# 20260106.net
KiCad netlist of a schematic drawn in EasyEDA Pro
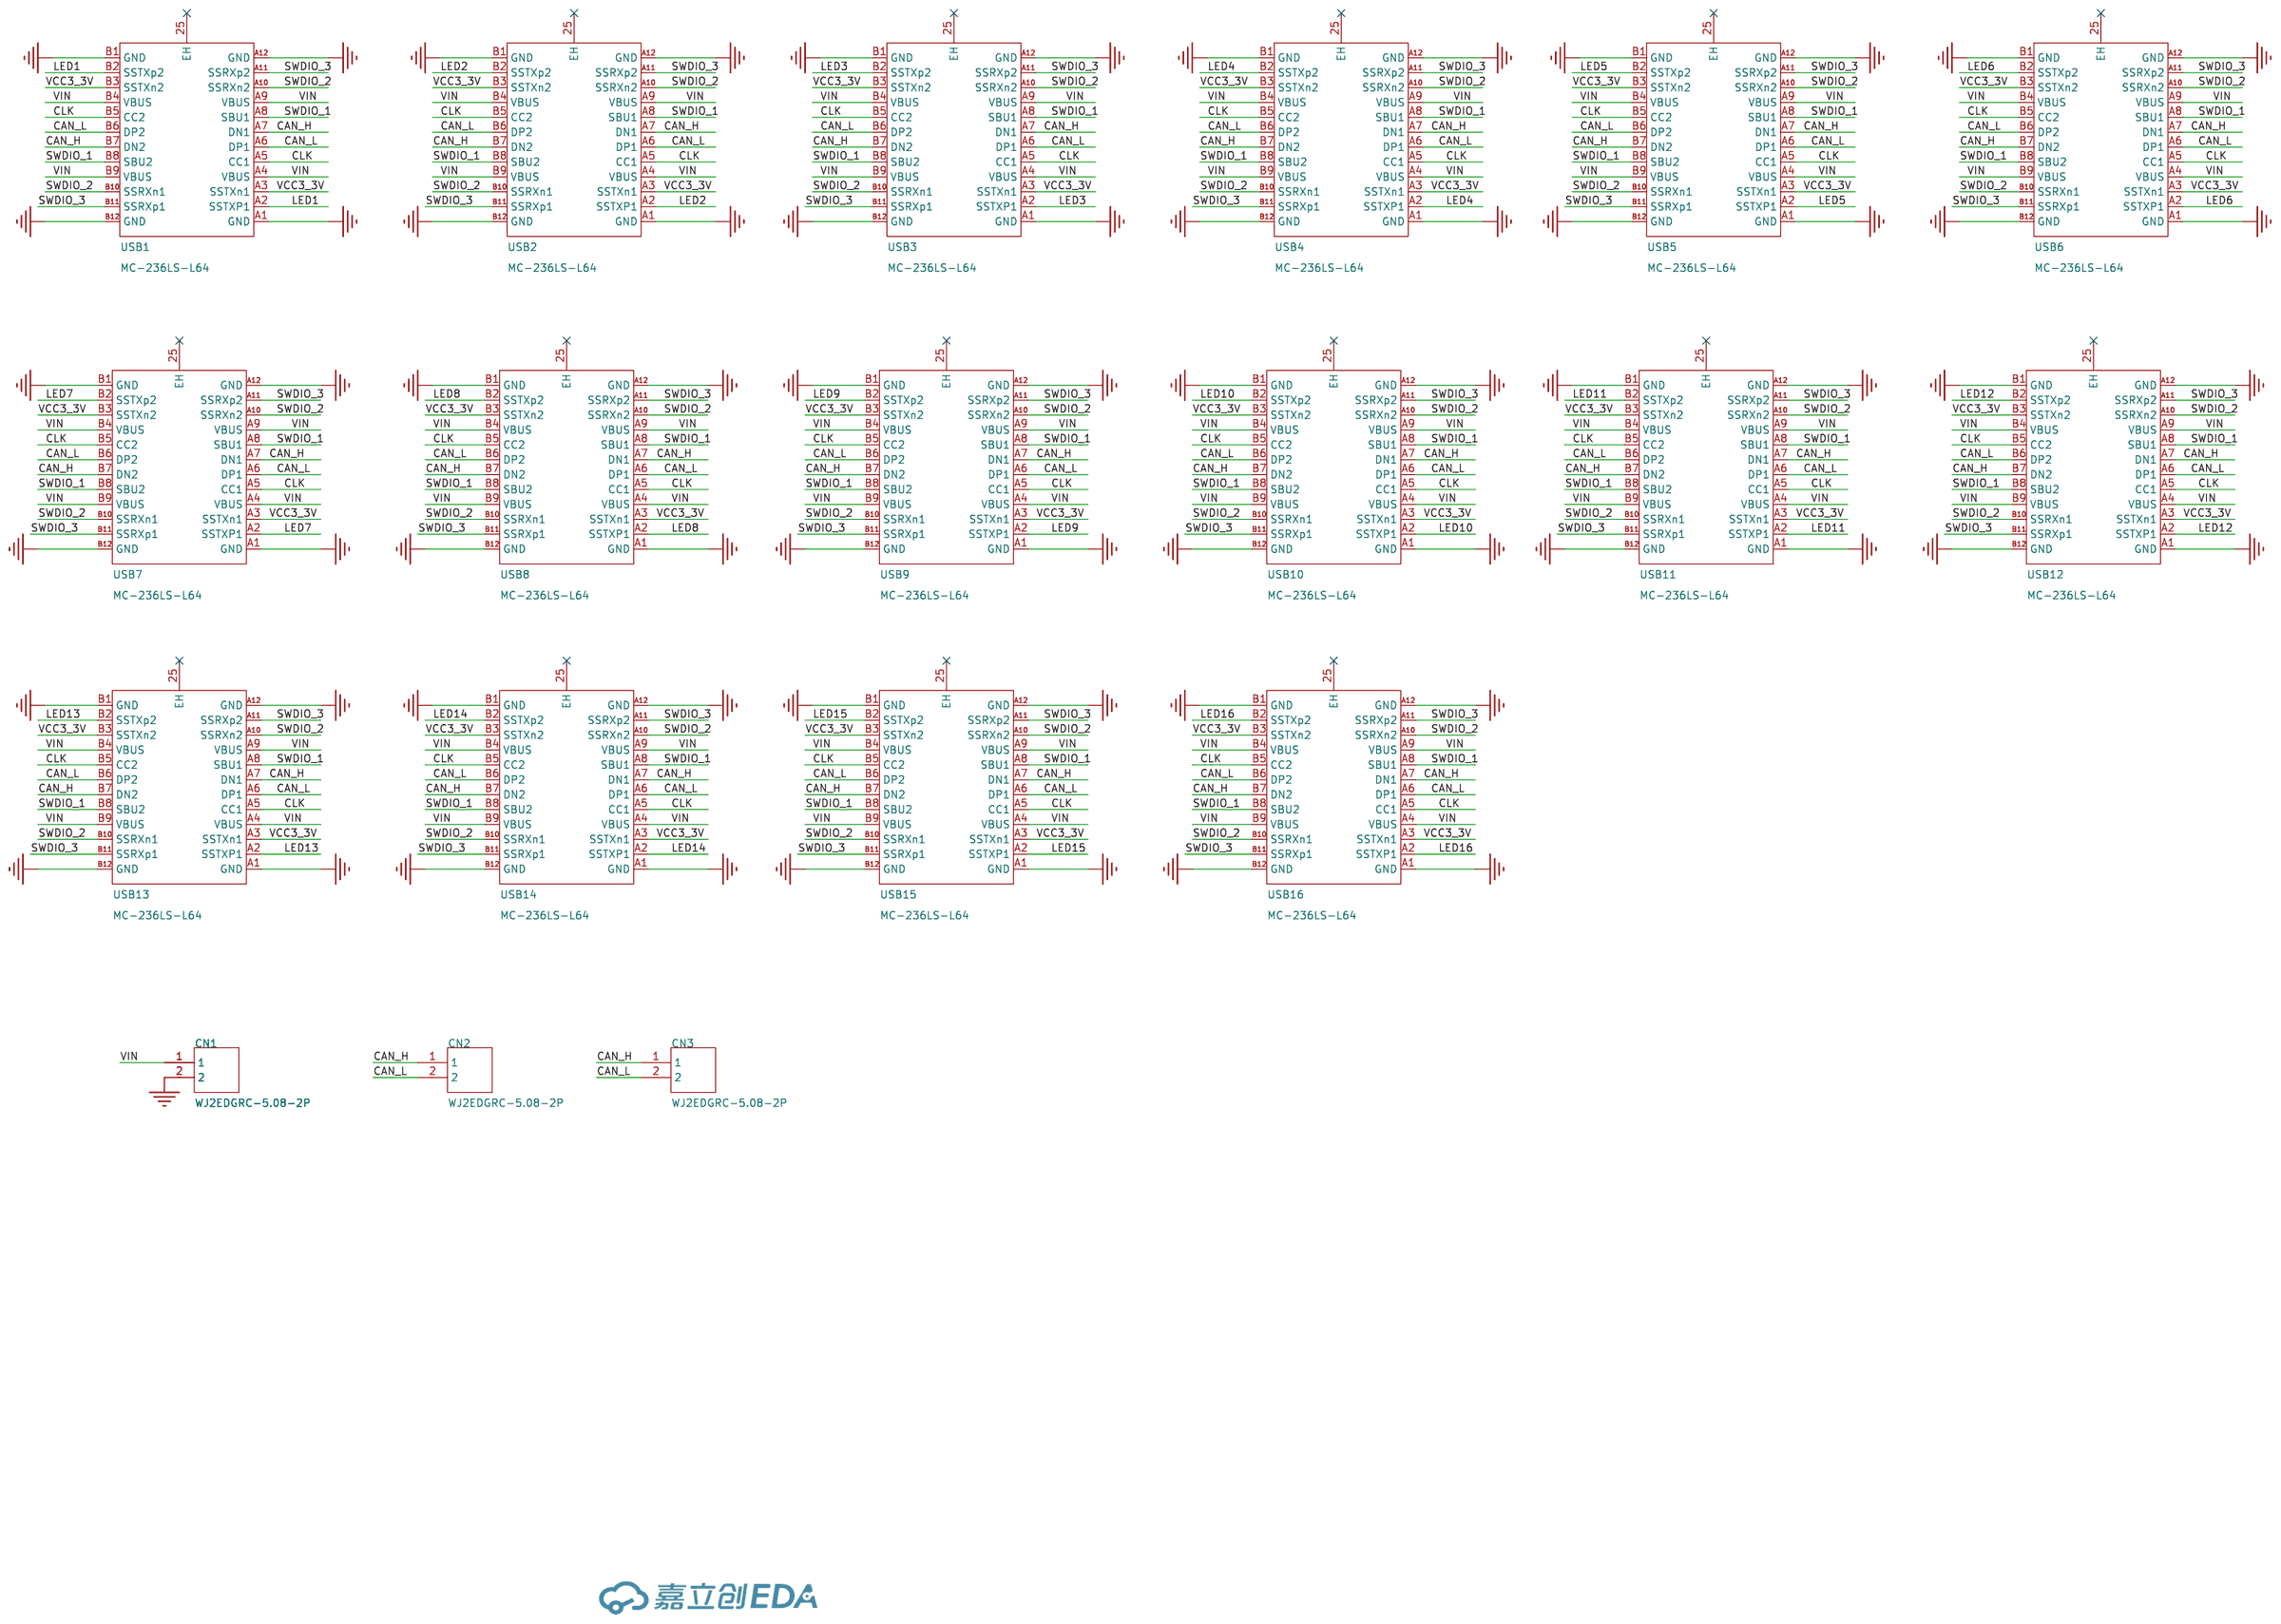
[diagram p0: schematic sheet]

(export (version "E")
  (design (tool "Eeschema 10.0.6"))
  (components
    (comp (ref "CN1")
      (value "WJ2EDGRC-5.08-2P")
      (footprint "easyedapro:CONN-TH_2P-P5.08_WJ2EDGRC-5.08-2P")
      (fields (field (name "Manufacturer") "KANGNEX(康奈克斯电气)"))
      (libsource (lib "easyedapro") (part "WJ2EDGRC-5.08-2P"))
    )
    (comp (ref "CN2")
      (value "WJ2EDGRC-5.08-2P")
      (footprint "easyedapro:CONN-TH_2P-P5.08_WJ2EDGRC-5.08-2P")
      (fields (field (name "Manufacturer") "KANGNEX(康奈克斯电气)"))
      (libsource (lib "easyedapro") (part "WJ2EDGRC-5.08-2P"))
    )
    (comp (ref "CN3")
      (value "WJ2EDGRC-5.08-2P")
      (footprint "easyedapro:CONN-TH_2P-P5.08_WJ2EDGRC-5.08-2P")
      (fields (field (name "Manufacturer") "KANGNEX(康奈克斯电气)"))
      (libsource (lib "easyedapro") (part "WJ2EDGRC-5.08-2P"))
    )
    (comp (ref "USB1")
      (value "MC-236LS-L64")
      (footprint "easyedapro:TYPE-C-USB-SMD_TYPE-C-31-M-06")
      (description "连接器类型:Type-C;协议标准:USB 3.1;公母:母;安装方式:立贴;触点数量:24P;端口数量:1;额定电流 - 电源:5A;工作温度:-25°C~+85°C;")
      (fields (field (name "Manufacturer") "HANBO(汉博)"))
      (libsource (lib "easyedapro") (part "MC-236LS-L64"))
    )
    (comp (ref "USB2")
      (value "MC-236LS-L64")
      (footprint "easyedapro:TYPE-C-USB-SMD_TYPE-C-31-M-06")
      (description "连接器类型:Type-C;协议标准:USB 3.1;公母:母;安装方式:立贴;触点数量:24P;端口数量:1;额定电流 - 电源:5A;工作温度:-25°C~+85°C;")
      (fields (field (name "Manufacturer") "HANBO(汉博)"))
      (libsource (lib "easyedapro") (part "MC-236LS-L64"))
    )
    (comp (ref "USB3")
      (value "MC-236LS-L64")
      (footprint "easyedapro:TYPE-C-USB-SMD_TYPE-C-31-M-06")
      (description "连接器类型:Type-C;协议标准:USB 3.1;公母:母;安装方式:立贴;触点数量:24P;端口数量:1;额定电流 - 电源:5A;工作温度:-25°C~+85°C;")
      (fields (field (name "Manufacturer") "HANBO(汉博)"))
      (libsource (lib "easyedapro") (part "MC-236LS-L64"))
    )
    (comp (ref "USB4")
      (value "MC-236LS-L64")
      (footprint "easyedapro:TYPE-C-USB-SMD_TYPE-C-31-M-06")
      (description "连接器类型:Type-C;协议标准:USB 3.1;公母:母;安装方式:立贴;触点数量:24P;端口数量:1;额定电流 - 电源:5A;工作温度:-25°C~+85°C;")
      (fields (field (name "Manufacturer") "HANBO(汉博)"))
      (libsource (lib "easyedapro") (part "MC-236LS-L64"))
    )
    (comp (ref "USB5")
      (value "MC-236LS-L64")
      (footprint "easyedapro:TYPE-C-USB-SMD_TYPE-C-31-M-06")
      (description "连接器类型:Type-C;协议标准:USB 3.1;公母:母;安装方式:立贴;触点数量:24P;端口数量:1;额定电流 - 电源:5A;工作温度:-25°C~+85°C;")
      (fields (field (name "Manufacturer") "HANBO(汉博)"))
      (libsource (lib "easyedapro") (part "MC-236LS-L64"))
    )
    (comp (ref "USB6")
      (value "MC-236LS-L64")
      (footprint "easyedapro:TYPE-C-USB-SMD_TYPE-C-31-M-06")
      (description "连接器类型:Type-C;协议标准:USB 3.1;公母:母;安装方式:立贴;触点数量:24P;端口数量:1;额定电流 - 电源:5A;工作温度:-25°C~+85°C;")
      (fields (field (name "Manufacturer") "HANBO(汉博)"))
      (libsource (lib "easyedapro") (part "MC-236LS-L64"))
    )
    (comp (ref "USB7")
      (value "MC-236LS-L64")
      (footprint "easyedapro:TYPE-C-USB-SMD_TYPE-C-31-M-06")
      (description "连接器类型:Type-C;协议标准:USB 3.1;公母:母;安装方式:立贴;触点数量:24P;端口数量:1;额定电流 - 电源:5A;工作温度:-25°C~+85°C;")
      (fields (field (name "Manufacturer") "HANBO(汉博)"))
      (libsource (lib "easyedapro") (part "MC-236LS-L64"))
    )
    (comp (ref "USB8")
      (value "MC-236LS-L64")
      (footprint "easyedapro:TYPE-C-USB-SMD_TYPE-C-31-M-06")
      (description "连接器类型:Type-C;协议标准:USB 3.1;公母:母;安装方式:立贴;触点数量:24P;端口数量:1;额定电流 - 电源:5A;工作温度:-25°C~+85°C;")
      (fields (field (name "Manufacturer") "HANBO(汉博)"))
      (libsource (lib "easyedapro") (part "MC-236LS-L64"))
    )
    (comp (ref "USB9")
      (value "MC-236LS-L64")
      (footprint "easyedapro:TYPE-C-USB-SMD_TYPE-C-31-M-06")
      (description "连接器类型:Type-C;协议标准:USB 3.1;公母:母;安装方式:立贴;触点数量:24P;端口数量:1;额定电流 - 电源:5A;工作温度:-25°C~+85°C;")
      (fields (field (name "Manufacturer") "HANBO(汉博)"))
      (libsource (lib "easyedapro") (part "MC-236LS-L64"))
    )
    (comp (ref "USB10")
      (value "MC-236LS-L64")
      (footprint "easyedapro:TYPE-C-USB-SMD_TYPE-C-31-M-06")
      (description "连接器类型:Type-C;协议标准:USB 3.1;公母:母;安装方式:立贴;触点数量:24P;端口数量:1;额定电流 - 电源:5A;工作温度:-25°C~+85°C;")
      (fields (field (name "Manufacturer") "HANBO(汉博)"))
      (libsource (lib "easyedapro") (part "MC-236LS-L64"))
    )
    (comp (ref "USB11")
      (value "MC-236LS-L64")
      (footprint "easyedapro:TYPE-C-USB-SMD_TYPE-C-31-M-06")
      (description "连接器类型:Type-C;协议标准:USB 3.1;公母:母;安装方式:立贴;触点数量:24P;端口数量:1;额定电流 - 电源:5A;工作温度:-25°C~+85°C;")
      (fields (field (name "Manufacturer") "HANBO(汉博)"))
      (libsource (lib "easyedapro") (part "MC-236LS-L64"))
    )
    (comp (ref "USB12")
      (value "MC-236LS-L64")
      (footprint "easyedapro:TYPE-C-USB-SMD_TYPE-C-31-M-06")
      (description "连接器类型:Type-C;协议标准:USB 3.1;公母:母;安装方式:立贴;触点数量:24P;端口数量:1;额定电流 - 电源:5A;工作温度:-25°C~+85°C;")
      (fields (field (name "Manufacturer") "HANBO(汉博)"))
      (libsource (lib "easyedapro") (part "MC-236LS-L64"))
    )
    (comp (ref "USB13")
      (value "MC-236LS-L64")
      (footprint "easyedapro:TYPE-C-USB-SMD_TYPE-C-31-M-06")
      (description "连接器类型:Type-C;协议标准:USB 3.1;公母:母;安装方式:立贴;触点数量:24P;端口数量:1;额定电流 - 电源:5A;工作温度:-25°C~+85°C;")
      (fields (field (name "Manufacturer") "HANBO(汉博)"))
      (libsource (lib "easyedapro") (part "MC-236LS-L64"))
    )
    (comp (ref "USB14")
      (value "MC-236LS-L64")
      (footprint "easyedapro:TYPE-C-USB-SMD_TYPE-C-31-M-06")
      (description "连接器类型:Type-C;协议标准:USB 3.1;公母:母;安装方式:立贴;触点数量:24P;端口数量:1;额定电流 - 电源:5A;工作温度:-25°C~+85°C;")
      (fields (field (name "Manufacturer") "HANBO(汉博)"))
      (libsource (lib "easyedapro") (part "MC-236LS-L64"))
    )
    (comp (ref "USB15")
      (value "MC-236LS-L64")
      (footprint "easyedapro:TYPE-C-USB-SMD_TYPE-C-31-M-06")
      (description "连接器类型:Type-C;协议标准:USB 3.1;公母:母;安装方式:立贴;触点数量:24P;端口数量:1;额定电流 - 电源:5A;工作温度:-25°C~+85°C;")
      (fields (field (name "Manufacturer") "HANBO(汉博)"))
      (libsource (lib "easyedapro") (part "MC-236LS-L64"))
    )
    (comp (ref "USB16")
      (value "MC-236LS-L64")
      (footprint "easyedapro:TYPE-C-USB-SMD_TYPE-C-31-M-06")
      (description "连接器类型:Type-C;协议标准:USB 3.1;公母:母;安装方式:立贴;触点数量:24P;端口数量:1;额定电流 - 电源:5A;工作温度:-25°C~+85°C;")
      (fields (field (name "Manufacturer") "HANBO(汉博)"))
      (libsource (lib "easyedapro") (part "MC-236LS-L64"))
    )
  )
  (nets
    (net (code "1") (name "/CAN_H") (class "Default")
      (node (ref "CN2") (pin "1") (pinfunction "1_1") (pintype "unspecified"))
      (node (ref "CN3") (pin "1") (pinfunction "1_1") (pintype "unspecified"))
      (node (ref "USB1") (pin "A7") (pinfunction "DN1_A7") (pintype "unspecified"))
      (node (ref "USB1") (pin "B7") (pinfunction "DN2_B7") (pintype "unspecified"))
      (node (ref "USB10") (pin "A7") (pinfunction "DN1_A7") (pintype "unspecified"))
      (node (ref "USB10") (pin "B7") (pinfunction "DN2_B7") (pintype "unspecified"))
      (node (ref "USB11") (pin "A7") (pinfunction "DN1_A7") (pintype "unspecified"))
      (node (ref "USB11") (pin "B7") (pinfunction "DN2_B7") (pintype "unspecified"))
      (node (ref "USB12") (pin "A7") (pinfunction "DN1_A7") (pintype "unspecified"))
      (node (ref "USB12") (pin "B7") (pinfunction "DN2_B7") (pintype "unspecified"))
      (node (ref "USB13") (pin "A7") (pinfunction "DN1_A7") (pintype "unspecified"))
      (node (ref "USB13") (pin "B7") (pinfunction "DN2_B7") (pintype "unspecified"))
      (node (ref "USB14") (pin "A7") (pinfunction "DN1_A7") (pintype "unspecified"))
      (node (ref "USB14") (pin "B7") (pinfunction "DN2_B7") (pintype "unspecified"))
      (node (ref "USB15") (pin "A7") (pinfunction "DN1_A7") (pintype "unspecified"))
      (node (ref "USB15") (pin "B7") (pinfunction "DN2_B7") (pintype "unspecified"))
      (node (ref "USB16") (pin "A7") (pinfunction "DN1_A7") (pintype "unspecified"))
      (node (ref "USB16") (pin "B7") (pinfunction "DN2_B7") (pintype "unspecified"))
      (node (ref "USB2") (pin "A7") (pinfunction "DN1_A7") (pintype "unspecified"))
      (node (ref "USB2") (pin "B7") (pinfunction "DN2_B7") (pintype "unspecified"))
      (node (ref "USB3") (pin "A7") (pinfunction "DN1_A7") (pintype "unspecified"))
      (node (ref "USB3") (pin "B7") (pinfunction "DN2_B7") (pintype "unspecified"))
      (node (ref "USB4") (pin "A7") (pinfunction "DN1_A7") (pintype "unspecified"))
      (node (ref "USB4") (pin "B7") (pinfunction "DN2_B7") (pintype "unspecified"))
      (node (ref "USB5") (pin "A7") (pinfunction "DN1_A7") (pintype "unspecified"))
      (node (ref "USB5") (pin "B7") (pinfunction "DN2_B7") (pintype "unspecified"))
      (node (ref "USB6") (pin "A7") (pinfunction "DN1_A7") (pintype "unspecified"))
      (node (ref "USB6") (pin "B7") (pinfunction "DN2_B7") (pintype "unspecified"))
      (node (ref "USB7") (pin "A7") (pinfunction "DN1_A7") (pintype "unspecified"))
      (node (ref "USB7") (pin "B7") (pinfunction "DN2_B7") (pintype "unspecified"))
      (node (ref "USB8") (pin "A7") (pinfunction "DN1_A7") (pintype "unspecified"))
      (node (ref "USB8") (pin "B7") (pinfunction "DN2_B7") (pintype "unspecified"))
      (node (ref "USB9") (pin "A7") (pinfunction "DN1_A7") (pintype "unspecified"))
      (node (ref "USB9") (pin "B7") (pinfunction "DN2_B7") (pintype "unspecified"))
    )
    (net (code "2") (name "/CAN_L") (class "Default")
      (node (ref "CN2") (pin "2") (pinfunction "2_2") (pintype "unspecified"))
      (node (ref "CN3") (pin "2") (pinfunction "2_2") (pintype "unspecified"))
      (node (ref "USB1") (pin "A6") (pinfunction "DP1_A6") (pintype "unspecified"))
      (node (ref "USB1") (pin "B6") (pinfunction "DP2_B6") (pintype "unspecified"))
      (node (ref "USB10") (pin "A6") (pinfunction "DP1_A6") (pintype "unspecified"))
      (node (ref "USB10") (pin "B6") (pinfunction "DP2_B6") (pintype "unspecified"))
      (node (ref "USB11") (pin "A6") (pinfunction "DP1_A6") (pintype "unspecified"))
      (node (ref "USB11") (pin "B6") (pinfunction "DP2_B6") (pintype "unspecified"))
      (node (ref "USB12") (pin "A6") (pinfunction "DP1_A6") (pintype "unspecified"))
      (node (ref "USB12") (pin "B6") (pinfunction "DP2_B6") (pintype "unspecified"))
      (node (ref "USB13") (pin "A6") (pinfunction "DP1_A6") (pintype "unspecified"))
      (node (ref "USB13") (pin "B6") (pinfunction "DP2_B6") (pintype "unspecified"))
      (node (ref "USB14") (pin "A6") (pinfunction "DP1_A6") (pintype "unspecified"))
      (node (ref "USB14") (pin "B6") (pinfunction "DP2_B6") (pintype "unspecified"))
      (node (ref "USB15") (pin "A6") (pinfunction "DP1_A6") (pintype "unspecified"))
      (node (ref "USB15") (pin "B6") (pinfunction "DP2_B6") (pintype "unspecified"))
      (node (ref "USB16") (pin "A6") (pinfunction "DP1_A6") (pintype "unspecified"))
      (node (ref "USB16") (pin "B6") (pinfunction "DP2_B6") (pintype "unspecified"))
      (node (ref "USB2") (pin "A6") (pinfunction "DP1_A6") (pintype "unspecified"))
      (node (ref "USB2") (pin "B6") (pinfunction "DP2_B6") (pintype "unspecified"))
      (node (ref "USB3") (pin "A6") (pinfunction "DP1_A6") (pintype "unspecified"))
      (node (ref "USB3") (pin "B6") (pinfunction "DP2_B6") (pintype "unspecified"))
      (node (ref "USB4") (pin "A6") (pinfunction "DP1_A6") (pintype "unspecified"))
      (node (ref "USB4") (pin "B6") (pinfunction "DP2_B6") (pintype "unspecified"))
      (node (ref "USB5") (pin "A6") (pinfunction "DP1_A6") (pintype "unspecified"))
      (node (ref "USB5") (pin "B6") (pinfunction "DP2_B6") (pintype "unspecified"))
      (node (ref "USB6") (pin "A6") (pinfunction "DP1_A6") (pintype "unspecified"))
      (node (ref "USB6") (pin "B6") (pinfunction "DP2_B6") (pintype "unspecified"))
      (node (ref "USB7") (pin "A6") (pinfunction "DP1_A6") (pintype "unspecified"))
      (node (ref "USB7") (pin "B6") (pinfunction "DP2_B6") (pintype "unspecified"))
      (node (ref "USB8") (pin "A6") (pinfunction "DP1_A6") (pintype "unspecified"))
      (node (ref "USB8") (pin "B6") (pinfunction "DP2_B6") (pintype "unspecified"))
      (node (ref "USB9") (pin "A6") (pinfunction "DP1_A6") (pintype "unspecified"))
      (node (ref "USB9") (pin "B6") (pinfunction "DP2_B6") (pintype "unspecified"))
    )
    (net (code "3") (name "/CLK") (class "Default")
      (node (ref "USB1") (pin "A5") (pinfunction "CC1_A5") (pintype "unspecified"))
      (node (ref "USB1") (pin "B5") (pinfunction "CC2_B5") (pintype "unspecified"))
      (node (ref "USB10") (pin "A5") (pinfunction "CC1_A5") (pintype "unspecified"))
      (node (ref "USB10") (pin "B5") (pinfunction "CC2_B5") (pintype "unspecified"))
      (node (ref "USB11") (pin "A5") (pinfunction "CC1_A5") (pintype "unspecified"))
      (node (ref "USB11") (pin "B5") (pinfunction "CC2_B5") (pintype "unspecified"))
      (node (ref "USB12") (pin "A5") (pinfunction "CC1_A5") (pintype "unspecified"))
      (node (ref "USB12") (pin "B5") (pinfunction "CC2_B5") (pintype "unspecified"))
      (node (ref "USB13") (pin "A5") (pinfunction "CC1_A5") (pintype "unspecified"))
      (node (ref "USB13") (pin "B5") (pinfunction "CC2_B5") (pintype "unspecified"))
      (node (ref "USB14") (pin "A5") (pinfunction "CC1_A5") (pintype "unspecified"))
      (node (ref "USB14") (pin "B5") (pinfunction "CC2_B5") (pintype "unspecified"))
      (node (ref "USB15") (pin "A5") (pinfunction "CC1_A5") (pintype "unspecified"))
      (node (ref "USB15") (pin "B5") (pinfunction "CC2_B5") (pintype "unspecified"))
      (node (ref "USB16") (pin "A5") (pinfunction "CC1_A5") (pintype "unspecified"))
      (node (ref "USB16") (pin "B5") (pinfunction "CC2_B5") (pintype "unspecified"))
      (node (ref "USB2") (pin "A5") (pinfunction "CC1_A5") (pintype "unspecified"))
      (node (ref "USB2") (pin "B5") (pinfunction "CC2_B5") (pintype "unspecified"))
      (node (ref "USB3") (pin "A5") (pinfunction "CC1_A5") (pintype "unspecified"))
      (node (ref "USB3") (pin "B5") (pinfunction "CC2_B5") (pintype "unspecified"))
      (node (ref "USB4") (pin "A5") (pinfunction "CC1_A5") (pintype "unspecified"))
      (node (ref "USB4") (pin "B5") (pinfunction "CC2_B5") (pintype "unspecified"))
      (node (ref "USB5") (pin "A5") (pinfunction "CC1_A5") (pintype "unspecified"))
      (node (ref "USB5") (pin "B5") (pinfunction "CC2_B5") (pintype "unspecified"))
      (node (ref "USB6") (pin "A5") (pinfunction "CC1_A5") (pintype "unspecified"))
      (node (ref "USB6") (pin "B5") (pinfunction "CC2_B5") (pintype "unspecified"))
      (node (ref "USB7") (pin "A5") (pinfunction "CC1_A5") (pintype "unspecified"))
      (node (ref "USB7") (pin "B5") (pinfunction "CC2_B5") (pintype "unspecified"))
      (node (ref "USB8") (pin "A5") (pinfunction "CC1_A5") (pintype "unspecified"))
      (node (ref "USB8") (pin "B5") (pinfunction "CC2_B5") (pintype "unspecified"))
      (node (ref "USB9") (pin "A5") (pinfunction "CC1_A5") (pintype "unspecified"))
      (node (ref "USB9") (pin "B5") (pinfunction "CC2_B5") (pintype "unspecified"))
    )
    (net (code "4") (name "/LED1") (class "Default")
      (node (ref "USB1") (pin "A2") (pinfunction "SSTXP1_A2") (pintype "unspecified"))
      (node (ref "USB1") (pin "B2") (pinfunction "SSTXp2_B2") (pintype "unspecified"))
    )
    (net (code "5") (name "/LED2") (class "Default")
      (node (ref "USB2") (pin "A2") (pinfunction "SSTXP1_A2") (pintype "unspecified"))
      (node (ref "USB2") (pin "B2") (pinfunction "SSTXp2_B2") (pintype "unspecified"))
    )
    (net (code "6") (name "/LED3") (class "Default")
      (node (ref "USB3") (pin "A2") (pinfunction "SSTXP1_A2") (pintype "unspecified"))
      (node (ref "USB3") (pin "B2") (pinfunction "SSTXp2_B2") (pintype "unspecified"))
    )
    (net (code "7") (name "/LED4") (class "Default")
      (node (ref "USB4") (pin "A2") (pinfunction "SSTXP1_A2") (pintype "unspecified"))
      (node (ref "USB4") (pin "B2") (pinfunction "SSTXp2_B2") (pintype "unspecified"))
    )
    (net (code "8") (name "/LED5") (class "Default")
      (node (ref "USB5") (pin "A2") (pinfunction "SSTXP1_A2") (pintype "unspecified"))
      (node (ref "USB5") (pin "B2") (pinfunction "SSTXp2_B2") (pintype "unspecified"))
    )
    (net (code "9") (name "/LED6") (class "Default")
      (node (ref "USB6") (pin "A2") (pinfunction "SSTXP1_A2") (pintype "unspecified"))
      (node (ref "USB6") (pin "B2") (pinfunction "SSTXp2_B2") (pintype "unspecified"))
    )
    (net (code "10") (name "/LED7") (class "Default")
      (node (ref "USB7") (pin "A2") (pinfunction "SSTXP1_A2") (pintype "unspecified"))
      (node (ref "USB7") (pin "B2") (pinfunction "SSTXp2_B2") (pintype "unspecified"))
    )
    (net (code "11") (name "/LED8") (class "Default")
      (node (ref "USB8") (pin "A2") (pinfunction "SSTXP1_A2") (pintype "unspecified"))
      (node (ref "USB8") (pin "B2") (pinfunction "SSTXp2_B2") (pintype "unspecified"))
    )
    (net (code "12") (name "/LED9") (class "Default")
      (node (ref "USB9") (pin "A2") (pinfunction "SSTXP1_A2") (pintype "unspecified"))
      (node (ref "USB9") (pin "B2") (pinfunction "SSTXp2_B2") (pintype "unspecified"))
    )
    (net (code "13") (name "/LED10") (class "Default")
      (node (ref "USB10") (pin "A2") (pinfunction "SSTXP1_A2") (pintype "unspecified"))
      (node (ref "USB10") (pin "B2") (pinfunction "SSTXp2_B2") (pintype "unspecified"))
    )
    (net (code "14") (name "/LED11") (class "Default")
      (node (ref "USB11") (pin "A2") (pinfunction "SSTXP1_A2") (pintype "unspecified"))
      (node (ref "USB11") (pin "B2") (pinfunction "SSTXp2_B2") (pintype "unspecified"))
    )
    (net (code "15") (name "/LED12") (class "Default")
      (node (ref "USB12") (pin "A2") (pinfunction "SSTXP1_A2") (pintype "unspecified"))
      (node (ref "USB12") (pin "B2") (pinfunction "SSTXp2_B2") (pintype "unspecified"))
    )
    (net (code "16") (name "/LED13") (class "Default")
      (node (ref "USB13") (pin "A2") (pinfunction "SSTXP1_A2") (pintype "unspecified"))
      (node (ref "USB13") (pin "B2") (pinfunction "SSTXp2_B2") (pintype "unspecified"))
    )
    (net (code "17") (name "/LED14") (class "Default")
      (node (ref "USB14") (pin "A2") (pinfunction "SSTXP1_A2") (pintype "unspecified"))
      (node (ref "USB14") (pin "B2") (pinfunction "SSTXp2_B2") (pintype "unspecified"))
    )
    (net (code "18") (name "/LED15") (class "Default")
      (node (ref "USB15") (pin "A2") (pinfunction "SSTXP1_A2") (pintype "unspecified"))
      (node (ref "USB15") (pin "B2") (pinfunction "SSTXp2_B2") (pintype "unspecified"))
    )
    (net (code "19") (name "/LED16") (class "Default")
      (node (ref "USB16") (pin "A2") (pinfunction "SSTXP1_A2") (pintype "unspecified"))
      (node (ref "USB16") (pin "B2") (pinfunction "SSTXp2_B2") (pintype "unspecified"))
    )
    (net (code "20") (name "/SWDIO_1") (class "Default")
      (node (ref "USB1") (pin "A8") (pinfunction "SBU1_A8") (pintype "unspecified"))
      (node (ref "USB1") (pin "B8") (pinfunction "SBU2_B8") (pintype "unspecified"))
      (node (ref "USB10") (pin "A8") (pinfunction "SBU1_A8") (pintype "unspecified"))
      (node (ref "USB10") (pin "B8") (pinfunction "SBU2_B8") (pintype "unspecified"))
      (node (ref "USB11") (pin "A8") (pinfunction "SBU1_A8") (pintype "unspecified"))
      (node (ref "USB11") (pin "B8") (pinfunction "SBU2_B8") (pintype "unspecified"))
      (node (ref "USB12") (pin "A8") (pinfunction "SBU1_A8") (pintype "unspecified"))
      (node (ref "USB12") (pin "B8") (pinfunction "SBU2_B8") (pintype "unspecified"))
      (node (ref "USB13") (pin "A8") (pinfunction "SBU1_A8") (pintype "unspecified"))
      (node (ref "USB13") (pin "B8") (pinfunction "SBU2_B8") (pintype "unspecified"))
      (node (ref "USB14") (pin "A8") (pinfunction "SBU1_A8") (pintype "unspecified"))
      (node (ref "USB14") (pin "B8") (pinfunction "SBU2_B8") (pintype "unspecified"))
      (node (ref "USB15") (pin "A8") (pinfunction "SBU1_A8") (pintype "unspecified"))
      (node (ref "USB15") (pin "B8") (pinfunction "SBU2_B8") (pintype "unspecified"))
      (node (ref "USB16") (pin "A8") (pinfunction "SBU1_A8") (pintype "unspecified"))
      (node (ref "USB16") (pin "B8") (pinfunction "SBU2_B8") (pintype "unspecified"))
      (node (ref "USB2") (pin "A8") (pinfunction "SBU1_A8") (pintype "unspecified"))
      (node (ref "USB2") (pin "B8") (pinfunction "SBU2_B8") (pintype "unspecified"))
      (node (ref "USB3") (pin "A8") (pinfunction "SBU1_A8") (pintype "unspecified"))
      (node (ref "USB3") (pin "B8") (pinfunction "SBU2_B8") (pintype "unspecified"))
      (node (ref "USB4") (pin "A8") (pinfunction "SBU1_A8") (pintype "unspecified"))
      (node (ref "USB4") (pin "B8") (pinfunction "SBU2_B8") (pintype "unspecified"))
      (node (ref "USB5") (pin "A8") (pinfunction "SBU1_A8") (pintype "unspecified"))
      (node (ref "USB5") (pin "B8") (pinfunction "SBU2_B8") (pintype "unspecified"))
      (node (ref "USB6") (pin "A8") (pinfunction "SBU1_A8") (pintype "unspecified"))
      (node (ref "USB6") (pin "B8") (pinfunction "SBU2_B8") (pintype "unspecified"))
      (node (ref "USB7") (pin "A8") (pinfunction "SBU1_A8") (pintype "unspecified"))
      (node (ref "USB7") (pin "B8") (pinfunction "SBU2_B8") (pintype "unspecified"))
      (node (ref "USB8") (pin "A8") (pinfunction "SBU1_A8") (pintype "unspecified"))
      (node (ref "USB8") (pin "B8") (pinfunction "SBU2_B8") (pintype "unspecified"))
      (node (ref "USB9") (pin "A8") (pinfunction "SBU1_A8") (pintype "unspecified"))
      (node (ref "USB9") (pin "B8") (pinfunction "SBU2_B8") (pintype "unspecified"))
    )
    (net (code "21") (name "/SWDIO_2") (class "Default")
      (node (ref "USB1") (pin "A10") (pinfunction "SSRXn2_A10") (pintype "unspecified"))
      (node (ref "USB1") (pin "B10") (pinfunction "SSRXn1_B10") (pintype "unspecified"))
      (node (ref "USB10") (pin "A10") (pinfunction "SSRXn2_A10") (pintype "unspecified"))
      (node (ref "USB10") (pin "B10") (pinfunction "SSRXn1_B10") (pintype "unspecified"))
      (node (ref "USB11") (pin "A10") (pinfunction "SSRXn2_A10") (pintype "unspecified"))
      (node (ref "USB11") (pin "B10") (pinfunction "SSRXn1_B10") (pintype "unspecified"))
      (node (ref "USB12") (pin "A10") (pinfunction "SSRXn2_A10") (pintype "unspecified"))
      (node (ref "USB12") (pin "B10") (pinfunction "SSRXn1_B10") (pintype "unspecified"))
      (node (ref "USB13") (pin "A10") (pinfunction "SSRXn2_A10") (pintype "unspecified"))
      (node (ref "USB13") (pin "B10") (pinfunction "SSRXn1_B10") (pintype "unspecified"))
      (node (ref "USB14") (pin "A10") (pinfunction "SSRXn2_A10") (pintype "unspecified"))
      (node (ref "USB14") (pin "B10") (pinfunction "SSRXn1_B10") (pintype "unspecified"))
      (node (ref "USB15") (pin "A10") (pinfunction "SSRXn2_A10") (pintype "unspecified"))
      (node (ref "USB15") (pin "B10") (pinfunction "SSRXn1_B10") (pintype "unspecified"))
      (node (ref "USB16") (pin "A10") (pinfunction "SSRXn2_A10") (pintype "unspecified"))
      (node (ref "USB16") (pin "B10") (pinfunction "SSRXn1_B10") (pintype "unspecified"))
      (node (ref "USB2") (pin "A10") (pinfunction "SSRXn2_A10") (pintype "unspecified"))
      (node (ref "USB2") (pin "B10") (pinfunction "SSRXn1_B10") (pintype "unspecified"))
      (node (ref "USB3") (pin "A10") (pinfunction "SSRXn2_A10") (pintype "unspecified"))
      (node (ref "USB3") (pin "B10") (pinfunction "SSRXn1_B10") (pintype "unspecified"))
      (node (ref "USB4") (pin "A10") (pinfunction "SSRXn2_A10") (pintype "unspecified"))
      (node (ref "USB4") (pin "B10") (pinfunction "SSRXn1_B10") (pintype "unspecified"))
      (node (ref "USB5") (pin "A10") (pinfunction "SSRXn2_A10") (pintype "unspecified"))
      (node (ref "USB5") (pin "B10") (pinfunction "SSRXn1_B10") (pintype "unspecified"))
      (node (ref "USB6") (pin "A10") (pinfunction "SSRXn2_A10") (pintype "unspecified"))
      (node (ref "USB6") (pin "B10") (pinfunction "SSRXn1_B10") (pintype "unspecified"))
      (node (ref "USB7") (pin "A10") (pinfunction "SSRXn2_A10") (pintype "unspecified"))
      (node (ref "USB7") (pin "B10") (pinfunction "SSRXn1_B10") (pintype "unspecified"))
      (node (ref "USB8") (pin "A10") (pinfunction "SSRXn2_A10") (pintype "unspecified"))
      (node (ref "USB8") (pin "B10") (pinfunction "SSRXn1_B10") (pintype "unspecified"))
      (node (ref "USB9") (pin "A10") (pinfunction "SSRXn2_A10") (pintype "unspecified"))
      (node (ref "USB9") (pin "B10") (pinfunction "SSRXn1_B10") (pintype "unspecified"))
    )
    (net (code "22") (name "/SWDIO_3") (class "Default")
      (node (ref "USB1") (pin "A11") (pinfunction "SSRXp2_A11") (pintype "unspecified"))
      (node (ref "USB1") (pin "B11") (pinfunction "SSRXp1_B11") (pintype "unspecified"))
      (node (ref "USB10") (pin "A11") (pinfunction "SSRXp2_A11") (pintype "unspecified"))
      (node (ref "USB10") (pin "B11") (pinfunction "SSRXp1_B11") (pintype "unspecified"))
      (node (ref "USB11") (pin "A11") (pinfunction "SSRXp2_A11") (pintype "unspecified"))
      (node (ref "USB11") (pin "B11") (pinfunction "SSRXp1_B11") (pintype "unspecified"))
      (node (ref "USB12") (pin "A11") (pinfunction "SSRXp2_A11") (pintype "unspecified"))
      (node (ref "USB12") (pin "B11") (pinfunction "SSRXp1_B11") (pintype "unspecified"))
      (node (ref "USB13") (pin "A11") (pinfunction "SSRXp2_A11") (pintype "unspecified"))
      (node (ref "USB13") (pin "B11") (pinfunction "SSRXp1_B11") (pintype "unspecified"))
      (node (ref "USB14") (pin "A11") (pinfunction "SSRXp2_A11") (pintype "unspecified"))
      (node (ref "USB14") (pin "B11") (pinfunction "SSRXp1_B11") (pintype "unspecified"))
      (node (ref "USB15") (pin "A11") (pinfunction "SSRXp2_A11") (pintype "unspecified"))
      (node (ref "USB15") (pin "B11") (pinfunction "SSRXp1_B11") (pintype "unspecified"))
      (node (ref "USB16") (pin "A11") (pinfunction "SSRXp2_A11") (pintype "unspecified"))
      (node (ref "USB16") (pin "B11") (pinfunction "SSRXp1_B11") (pintype "unspecified"))
      (node (ref "USB2") (pin "A11") (pinfunction "SSRXp2_A11") (pintype "unspecified"))
      (node (ref "USB2") (pin "B11") (pinfunction "SSRXp1_B11") (pintype "unspecified"))
      (node (ref "USB3") (pin "A11") (pinfunction "SSRXp2_A11") (pintype "unspecified"))
      (node (ref "USB3") (pin "B11") (pinfunction "SSRXp1_B11") (pintype "unspecified"))
      (node (ref "USB4") (pin "A11") (pinfunction "SSRXp2_A11") (pintype "unspecified"))
      (node (ref "USB4") (pin "B11") (pinfunction "SSRXp1_B11") (pintype "unspecified"))
      (node (ref "USB5") (pin "A11") (pinfunction "SSRXp2_A11") (pintype "unspecified"))
      (node (ref "USB5") (pin "B11") (pinfunction "SSRXp1_B11") (pintype "unspecified"))
      (node (ref "USB6") (pin "A11") (pinfunction "SSRXp2_A11") (pintype "unspecified"))
      (node (ref "USB6") (pin "B11") (pinfunction "SSRXp1_B11") (pintype "unspecified"))
      (node (ref "USB7") (pin "A11") (pinfunction "SSRXp2_A11") (pintype "unspecified"))
      (node (ref "USB7") (pin "B11") (pinfunction "SSRXp1_B11") (pintype "unspecified"))
      (node (ref "USB8") (pin "A11") (pinfunction "SSRXp2_A11") (pintype "unspecified"))
      (node (ref "USB8") (pin "B11") (pinfunction "SSRXp1_B11") (pintype "unspecified"))
      (node (ref "USB9") (pin "A11") (pinfunction "SSRXp2_A11") (pintype "unspecified"))
      (node (ref "USB9") (pin "B11") (pinfunction "SSRXp1_B11") (pintype "unspecified"))
    )
    (net (code "23") (name "/VCC3_3V") (class "Default")
      (node (ref "USB1") (pin "A3") (pinfunction "SSTXn1_A3") (pintype "unspecified"))
      (node (ref "USB1") (pin "B3") (pinfunction "SSTXn2_B3") (pintype "unspecified"))
      (node (ref "USB10") (pin "A3") (pinfunction "SSTXn1_A3") (pintype "unspecified"))
      (node (ref "USB10") (pin "B3") (pinfunction "SSTXn2_B3") (pintype "unspecified"))
      (node (ref "USB11") (pin "A3") (pinfunction "SSTXn1_A3") (pintype "unspecified"))
      (node (ref "USB11") (pin "B3") (pinfunction "SSTXn2_B3") (pintype "unspecified"))
      (node (ref "USB12") (pin "A3") (pinfunction "SSTXn1_A3") (pintype "unspecified"))
      (node (ref "USB12") (pin "B3") (pinfunction "SSTXn2_B3") (pintype "unspecified"))
      (node (ref "USB13") (pin "A3") (pinfunction "SSTXn1_A3") (pintype "unspecified"))
      (node (ref "USB13") (pin "B3") (pinfunction "SSTXn2_B3") (pintype "unspecified"))
      (node (ref "USB14") (pin "A3") (pinfunction "SSTXn1_A3") (pintype "unspecified"))
      (node (ref "USB14") (pin "B3") (pinfunction "SSTXn2_B3") (pintype "unspecified"))
      (node (ref "USB15") (pin "A3") (pinfunction "SSTXn1_A3") (pintype "unspecified"))
      (node (ref "USB15") (pin "B3") (pinfunction "SSTXn2_B3") (pintype "unspecified"))
      (node (ref "USB16") (pin "A3") (pinfunction "SSTXn1_A3") (pintype "unspecified"))
      (node (ref "USB16") (pin "B3") (pinfunction "SSTXn2_B3") (pintype "unspecified"))
      (node (ref "USB2") (pin "A3") (pinfunction "SSTXn1_A3") (pintype "unspecified"))
      (node (ref "USB2") (pin "B3") (pinfunction "SSTXn2_B3") (pintype "unspecified"))
      (node (ref "USB3") (pin "A3") (pinfunction "SSTXn1_A3") (pintype "unspecified"))
      (node (ref "USB3") (pin "B3") (pinfunction "SSTXn2_B3") (pintype "unspecified"))
      (node (ref "USB4") (pin "A3") (pinfunction "SSTXn1_A3") (pintype "unspecified"))
      (node (ref "USB4") (pin "B3") (pinfunction "SSTXn2_B3") (pintype "unspecified"))
      (node (ref "USB5") (pin "A3") (pinfunction "SSTXn1_A3") (pintype "unspecified"))
      (node (ref "USB5") (pin "B3") (pinfunction "SSTXn2_B3") (pintype "unspecified"))
      (node (ref "USB6") (pin "A3") (pinfunction "SSTXn1_A3") (pintype "unspecified"))
      (node (ref "USB6") (pin "B3") (pinfunction "SSTXn2_B3") (pintype "unspecified"))
      (node (ref "USB7") (pin "A3") (pinfunction "SSTXn1_A3") (pintype "unspecified"))
      (node (ref "USB7") (pin "B3") (pinfunction "SSTXn2_B3") (pintype "unspecified"))
      (node (ref "USB8") (pin "A3") (pinfunction "SSTXn1_A3") (pintype "unspecified"))
      (node (ref "USB8") (pin "B3") (pinfunction "SSTXn2_B3") (pintype "unspecified"))
      (node (ref "USB9") (pin "A3") (pinfunction "SSTXn1_A3") (pintype "unspecified"))
      (node (ref "USB9") (pin "B3") (pinfunction "SSTXn2_B3") (pintype "unspecified"))
    )
    (net (code "24") (name "/VIN") (class "Default")
      (node (ref "CN1") (pin "1") (pinfunction "1_1") (pintype "unspecified"))
      (node (ref "USB1") (pin "A4") (pinfunction "VBUS_A4") (pintype "unspecified"))
      (node (ref "USB1") (pin "A9") (pinfunction "VBUS_A9") (pintype "unspecified"))
      (node (ref "USB1") (pin "B4") (pinfunction "VBUS_B4") (pintype "unspecified"))
      (node (ref "USB1") (pin "B9") (pinfunction "VBUS_B9") (pintype "unspecified"))
      (node (ref "USB10") (pin "A4") (pinfunction "VBUS_A4") (pintype "unspecified"))
      (node (ref "USB10") (pin "A9") (pinfunction "VBUS_A9") (pintype "unspecified"))
      (node (ref "USB10") (pin "B4") (pinfunction "VBUS_B4") (pintype "unspecified"))
      (node (ref "USB10") (pin "B9") (pinfunction "VBUS_B9") (pintype "unspecified"))
      (node (ref "USB11") (pin "A4") (pinfunction "VBUS_A4") (pintype "unspecified"))
      (node (ref "USB11") (pin "A9") (pinfunction "VBUS_A9") (pintype "unspecified"))
      (node (ref "USB11") (pin "B4") (pinfunction "VBUS_B4") (pintype "unspecified"))
      (node (ref "USB11") (pin "B9") (pinfunction "VBUS_B9") (pintype "unspecified"))
      (node (ref "USB12") (pin "A4") (pinfunction "VBUS_A4") (pintype "unspecified"))
      (node (ref "USB12") (pin "A9") (pinfunction "VBUS_A9") (pintype "unspecified"))
      (node (ref "USB12") (pin "B4") (pinfunction "VBUS_B4") (pintype "unspecified"))
      (node (ref "USB12") (pin "B9") (pinfunction "VBUS_B9") (pintype "unspecified"))
      (node (ref "USB13") (pin "A4") (pinfunction "VBUS_A4") (pintype "unspecified"))
      (node (ref "USB13") (pin "A9") (pinfunction "VBUS_A9") (pintype "unspecified"))
      (node (ref "USB13") (pin "B4") (pinfunction "VBUS_B4") (pintype "unspecified"))
      (node (ref "USB13") (pin "B9") (pinfunction "VBUS_B9") (pintype "unspecified"))
      (node (ref "USB14") (pin "A4") (pinfunction "VBUS_A4") (pintype "unspecified"))
      (node (ref "USB14") (pin "A9") (pinfunction "VBUS_A9") (pintype "unspecified"))
      (node (ref "USB14") (pin "B4") (pinfunction "VBUS_B4") (pintype "unspecified"))
      (node (ref "USB14") (pin "B9") (pinfunction "VBUS_B9") (pintype "unspecified"))
      (node (ref "USB15") (pin "A4") (pinfunction "VBUS_A4") (pintype "unspecified"))
      (node (ref "USB15") (pin "A9") (pinfunction "VBUS_A9") (pintype "unspecified"))
      (node (ref "USB15") (pin "B4") (pinfunction "VBUS_B4") (pintype "unspecified"))
      (node (ref "USB15") (pin "B9") (pinfunction "VBUS_B9") (pintype "unspecified"))
      (node (ref "USB16") (pin "A4") (pinfunction "VBUS_A4") (pintype "unspecified"))
      (node (ref "USB16") (pin "A9") (pinfunction "VBUS_A9") (pintype "unspecified"))
      (node (ref "USB16") (pin "B4") (pinfunction "VBUS_B4") (pintype "unspecified"))
      (node (ref "USB16") (pin "B9") (pinfunction "VBUS_B9") (pintype "unspecified"))
      (node (ref "USB2") (pin "A4") (pinfunction "VBUS_A4") (pintype "unspecified"))
      (node (ref "USB2") (pin "A9") (pinfunction "VBUS_A9") (pintype "unspecified"))
      (node (ref "USB2") (pin "B4") (pinfunction "VBUS_B4") (pintype "unspecified"))
      (node (ref "USB2") (pin "B9") (pinfunction "VBUS_B9") (pintype "unspecified"))
      (node (ref "USB3") (pin "A4") (pinfunction "VBUS_A4") (pintype "unspecified"))
      (node (ref "USB3") (pin "A9") (pinfunction "VBUS_A9") (pintype "unspecified"))
      (node (ref "USB3") (pin "B4") (pinfunction "VBUS_B4") (pintype "unspecified"))
      (node (ref "USB3") (pin "B9") (pinfunction "VBUS_B9") (pintype "unspecified"))
      (node (ref "USB4") (pin "A4") (pinfunction "VBUS_A4") (pintype "unspecified"))
      (node (ref "USB4") (pin "A9") (pinfunction "VBUS_A9") (pintype "unspecified"))
      (node (ref "USB4") (pin "B4") (pinfunction "VBUS_B4") (pintype "unspecified"))
      (node (ref "USB4") (pin "B9") (pinfunction "VBUS_B9") (pintype "unspecified"))
      (node (ref "USB5") (pin "A4") (pinfunction "VBUS_A4") (pintype "unspecified"))
      (node (ref "USB5") (pin "A9") (pinfunction "VBUS_A9") (pintype "unspecified"))
      (node (ref "USB5") (pin "B4") (pinfunction "VBUS_B4") (pintype "unspecified"))
      (node (ref "USB5") (pin "B9") (pinfunction "VBUS_B9") (pintype "unspecified"))
      (node (ref "USB6") (pin "A4") (pinfunction "VBUS_A4") (pintype "unspecified"))
      (node (ref "USB6") (pin "A9") (pinfunction "VBUS_A9") (pintype "unspecified"))
      (node (ref "USB6") (pin "B4") (pinfunction "VBUS_B4") (pintype "unspecified"))
      (node (ref "USB6") (pin "B9") (pinfunction "VBUS_B9") (pintype "unspecified"))
      (node (ref "USB7") (pin "A4") (pinfunction "VBUS_A4") (pintype "unspecified"))
      (node (ref "USB7") (pin "A9") (pinfunction "VBUS_A9") (pintype "unspecified"))
      (node (ref "USB7") (pin "B4") (pinfunction "VBUS_B4") (pintype "unspecified"))
      (node (ref "USB7") (pin "B9") (pinfunction "VBUS_B9") (pintype "unspecified"))
      (node (ref "USB8") (pin "A4") (pinfunction "VBUS_A4") (pintype "unspecified"))
      (node (ref "USB8") (pin "A9") (pinfunction "VBUS_A9") (pintype "unspecified"))
      (node (ref "USB8") (pin "B4") (pinfunction "VBUS_B4") (pintype "unspecified"))
      (node (ref "USB8") (pin "B9") (pinfunction "VBUS_B9") (pintype "unspecified"))
      (node (ref "USB9") (pin "A4") (pinfunction "VBUS_A4") (pintype "unspecified"))
      (node (ref "USB9") (pin "A9") (pinfunction "VBUS_A9") (pintype "unspecified"))
      (node (ref "USB9") (pin "B4") (pinfunction "VBUS_B4") (pintype "unspecified"))
      (node (ref "USB9") (pin "B9") (pinfunction "VBUS_B9") (pintype "unspecified"))
    )
    (net (code "25") (name "GND") (class "Default")
      (node (ref "CN1") (pin "2") (pinfunction "2_2") (pintype "unspecified"))
      (node (ref "USB1") (pin "A1") (pinfunction "GND_A1") (pintype "unspecified"))
      (node (ref "USB1") (pin "A12") (pinfunction "GND_A12") (pintype "unspecified"))
      (node (ref "USB1") (pin "B1") (pinfunction "GND_B1") (pintype "unspecified"))
      (node (ref "USB1") (pin "B12") (pinfunction "GND_B12") (pintype "unspecified"))
      (node (ref "USB10") (pin "A1") (pinfunction "GND_A1") (pintype "unspecified"))
      (node (ref "USB10") (pin "A12") (pinfunction "GND_A12") (pintype "unspecified"))
      (node (ref "USB10") (pin "B1") (pinfunction "GND_B1") (pintype "unspecified"))
      (node (ref "USB10") (pin "B12") (pinfunction "GND_B12") (pintype "unspecified"))
      (node (ref "USB11") (pin "A1") (pinfunction "GND_A1") (pintype "unspecified"))
      (node (ref "USB11") (pin "A12") (pinfunction "GND_A12") (pintype "unspecified"))
      (node (ref "USB11") (pin "B1") (pinfunction "GND_B1") (pintype "unspecified"))
      (node (ref "USB11") (pin "B12") (pinfunction "GND_B12") (pintype "unspecified"))
      (node (ref "USB12") (pin "A1") (pinfunction "GND_A1") (pintype "unspecified"))
      (node (ref "USB12") (pin "A12") (pinfunction "GND_A12") (pintype "unspecified"))
      (node (ref "USB12") (pin "B1") (pinfunction "GND_B1") (pintype "unspecified"))
      (node (ref "USB12") (pin "B12") (pinfunction "GND_B12") (pintype "unspecified"))
      (node (ref "USB13") (pin "A1") (pinfunction "GND_A1") (pintype "unspecified"))
      (node (ref "USB13") (pin "A12") (pinfunction "GND_A12") (pintype "unspecified"))
      (node (ref "USB13") (pin "B1") (pinfunction "GND_B1") (pintype "unspecified"))
      (node (ref "USB13") (pin "B12") (pinfunction "GND_B12") (pintype "unspecified"))
      (node (ref "USB14") (pin "A1") (pinfunction "GND_A1") (pintype "unspecified"))
      (node (ref "USB14") (pin "A12") (pinfunction "GND_A12") (pintype "unspecified"))
      (node (ref "USB14") (pin "B1") (pinfunction "GND_B1") (pintype "unspecified"))
      (node (ref "USB14") (pin "B12") (pinfunction "GND_B12") (pintype "unspecified"))
      (node (ref "USB15") (pin "A1") (pinfunction "GND_A1") (pintype "unspecified"))
      (node (ref "USB15") (pin "A12") (pinfunction "GND_A12") (pintype "unspecified"))
      (node (ref "USB15") (pin "B1") (pinfunction "GND_B1") (pintype "unspecified"))
      (node (ref "USB15") (pin "B12") (pinfunction "GND_B12") (pintype "unspecified"))
      (node (ref "USB16") (pin "A1") (pinfunction "GND_A1") (pintype "unspecified"))
      (node (ref "USB16") (pin "A12") (pinfunction "GND_A12") (pintype "unspecified"))
      (node (ref "USB16") (pin "B1") (pinfunction "GND_B1") (pintype "unspecified"))
      (node (ref "USB16") (pin "B12") (pinfunction "GND_B12") (pintype "unspecified"))
      (node (ref "USB2") (pin "A1") (pinfunction "GND_A1") (pintype "unspecified"))
      (node (ref "USB2") (pin "A12") (pinfunction "GND_A12") (pintype "unspecified"))
      (node (ref "USB2") (pin "B1") (pinfunction "GND_B1") (pintype "unspecified"))
      (node (ref "USB2") (pin "B12") (pinfunction "GND_B12") (pintype "unspecified"))
      (node (ref "USB3") (pin "A1") (pinfunction "GND_A1") (pintype "unspecified"))
      (node (ref "USB3") (pin "A12") (pinfunction "GND_A12") (pintype "unspecified"))
      (node (ref "USB3") (pin "B1") (pinfunction "GND_B1") (pintype "unspecified"))
      (node (ref "USB3") (pin "B12") (pinfunction "GND_B12") (pintype "unspecified"))
      (node (ref "USB4") (pin "A1") (pinfunction "GND_A1") (pintype "unspecified"))
      (node (ref "USB4") (pin "A12") (pinfunction "GND_A12") (pintype "unspecified"))
      (node (ref "USB4") (pin "B1") (pinfunction "GND_B1") (pintype "unspecified"))
      (node (ref "USB4") (pin "B12") (pinfunction "GND_B12") (pintype "unspecified"))
      (node (ref "USB5") (pin "A1") (pinfunction "GND_A1") (pintype "unspecified"))
      (node (ref "USB5") (pin "A12") (pinfunction "GND_A12") (pintype "unspecified"))
      (node (ref "USB5") (pin "B1") (pinfunction "GND_B1") (pintype "unspecified"))
      (node (ref "USB5") (pin "B12") (pinfunction "GND_B12") (pintype "unspecified"))
      (node (ref "USB6") (pin "A1") (pinfunction "GND_A1") (pintype "unspecified"))
      (node (ref "USB6") (pin "A12") (pinfunction "GND_A12") (pintype "unspecified"))
      (node (ref "USB6") (pin "B1") (pinfunction "GND_B1") (pintype "unspecified"))
      (node (ref "USB6") (pin "B12") (pinfunction "GND_B12") (pintype "unspecified"))
      (node (ref "USB7") (pin "A1") (pinfunction "GND_A1") (pintype "unspecified"))
      (node (ref "USB7") (pin "A12") (pinfunction "GND_A12") (pintype "unspecified"))
      (node (ref "USB7") (pin "B1") (pinfunction "GND_B1") (pintype "unspecified"))
      (node (ref "USB7") (pin "B12") (pinfunction "GND_B12") (pintype "unspecified"))
      (node (ref "USB8") (pin "A1") (pinfunction "GND_A1") (pintype "unspecified"))
      (node (ref "USB8") (pin "A12") (pinfunction "GND_A12") (pintype "unspecified"))
      (node (ref "USB8") (pin "B1") (pinfunction "GND_B1") (pintype "unspecified"))
      (node (ref "USB8") (pin "B12") (pinfunction "GND_B12") (pintype "unspecified"))
      (node (ref "USB9") (pin "A1") (pinfunction "GND_A1") (pintype "unspecified"))
      (node (ref "USB9") (pin "A12") (pinfunction "GND_A12") (pintype "unspecified"))
      (node (ref "USB9") (pin "B1") (pinfunction "GND_B1") (pintype "unspecified"))
      (node (ref "USB9") (pin "B12") (pinfunction "GND_B12") (pintype "unspecified"))
    )
    (net (code "26") (name "unconnected-(USB1-EH-Pad25)") (class "Default")
      (node (ref "USB1") (pin "25") (pinfunction "EH_25") (pintype "unspecified+no_connect"))
    )
    (net (code "27") (name "unconnected-(USB2-EH-Pad25)") (class "Default")
      (node (ref "USB2") (pin "25") (pinfunction "EH_25") (pintype "unspecified+no_connect"))
    )
    (net (code "28") (name "unconnected-(USB3-EH-Pad25)") (class "Default")
      (node (ref "USB3") (pin "25") (pinfunction "EH_25") (pintype "unspecified+no_connect"))
    )
    (net (code "29") (name "unconnected-(USB4-EH-Pad25)") (class "Default")
      (node (ref "USB4") (pin "25") (pinfunction "EH_25") (pintype "unspecified+no_connect"))
    )
    (net (code "30") (name "unconnected-(USB5-EH-Pad25)") (class "Default")
      (node (ref "USB5") (pin "25") (pinfunction "EH_25") (pintype "unspecified+no_connect"))
    )
    (net (code "31") (name "unconnected-(USB6-EH-Pad25)") (class "Default")
      (node (ref "USB6") (pin "25") (pinfunction "EH_25") (pintype "unspecified+no_connect"))
    )
    (net (code "32") (name "unconnected-(USB7-EH-Pad25)") (class "Default")
      (node (ref "USB7") (pin "25") (pinfunction "EH_25") (pintype "unspecified+no_connect"))
    )
    (net (code "33") (name "unconnected-(USB8-EH-Pad25)") (class "Default")
      (node (ref "USB8") (pin "25") (pinfunction "EH_25") (pintype "unspecified+no_connect"))
    )
    (net (code "34") (name "unconnected-(USB9-EH-Pad25)") (class "Default")
      (node (ref "USB9") (pin "25") (pinfunction "EH_25") (pintype "unspecified+no_connect"))
    )
    (net (code "35") (name "unconnected-(USB10-EH-Pad25)") (class "Default")
      (node (ref "USB10") (pin "25") (pinfunction "EH_25") (pintype "unspecified+no_connect"))
    )
    (net (code "36") (name "unconnected-(USB11-EH-Pad25)") (class "Default")
      (node (ref "USB11") (pin "25") (pinfunction "EH_25") (pintype "unspecified+no_connect"))
    )
    (net (code "37") (name "unconnected-(USB12-EH-Pad25)") (class "Default")
      (node (ref "USB12") (pin "25") (pinfunction "EH_25") (pintype "unspecified+no_connect"))
    )
    (net (code "38") (name "unconnected-(USB13-EH-Pad25)") (class "Default")
      (node (ref "USB13") (pin "25") (pinfunction "EH_25") (pintype "unspecified+no_connect"))
    )
    (net (code "39") (name "unconnected-(USB14-EH-Pad25)") (class "Default")
      (node (ref "USB14") (pin "25") (pinfunction "EH_25") (pintype "unspecified+no_connect"))
    )
    (net (code "40") (name "unconnected-(USB15-EH-Pad25)") (class "Default")
      (node (ref "USB15") (pin "25") (pinfunction "EH_25") (pintype "unspecified+no_connect"))
    )
    (net (code "41") (name "unconnected-(USB16-EH-Pad25)") (class "Default")
      (node (ref "USB16") (pin "25") (pinfunction "EH_25") (pintype "unspecified+no_connect"))
    )
  )
)
